# Main.net
KiCad netlist of a schematic drawn in Altium Designer
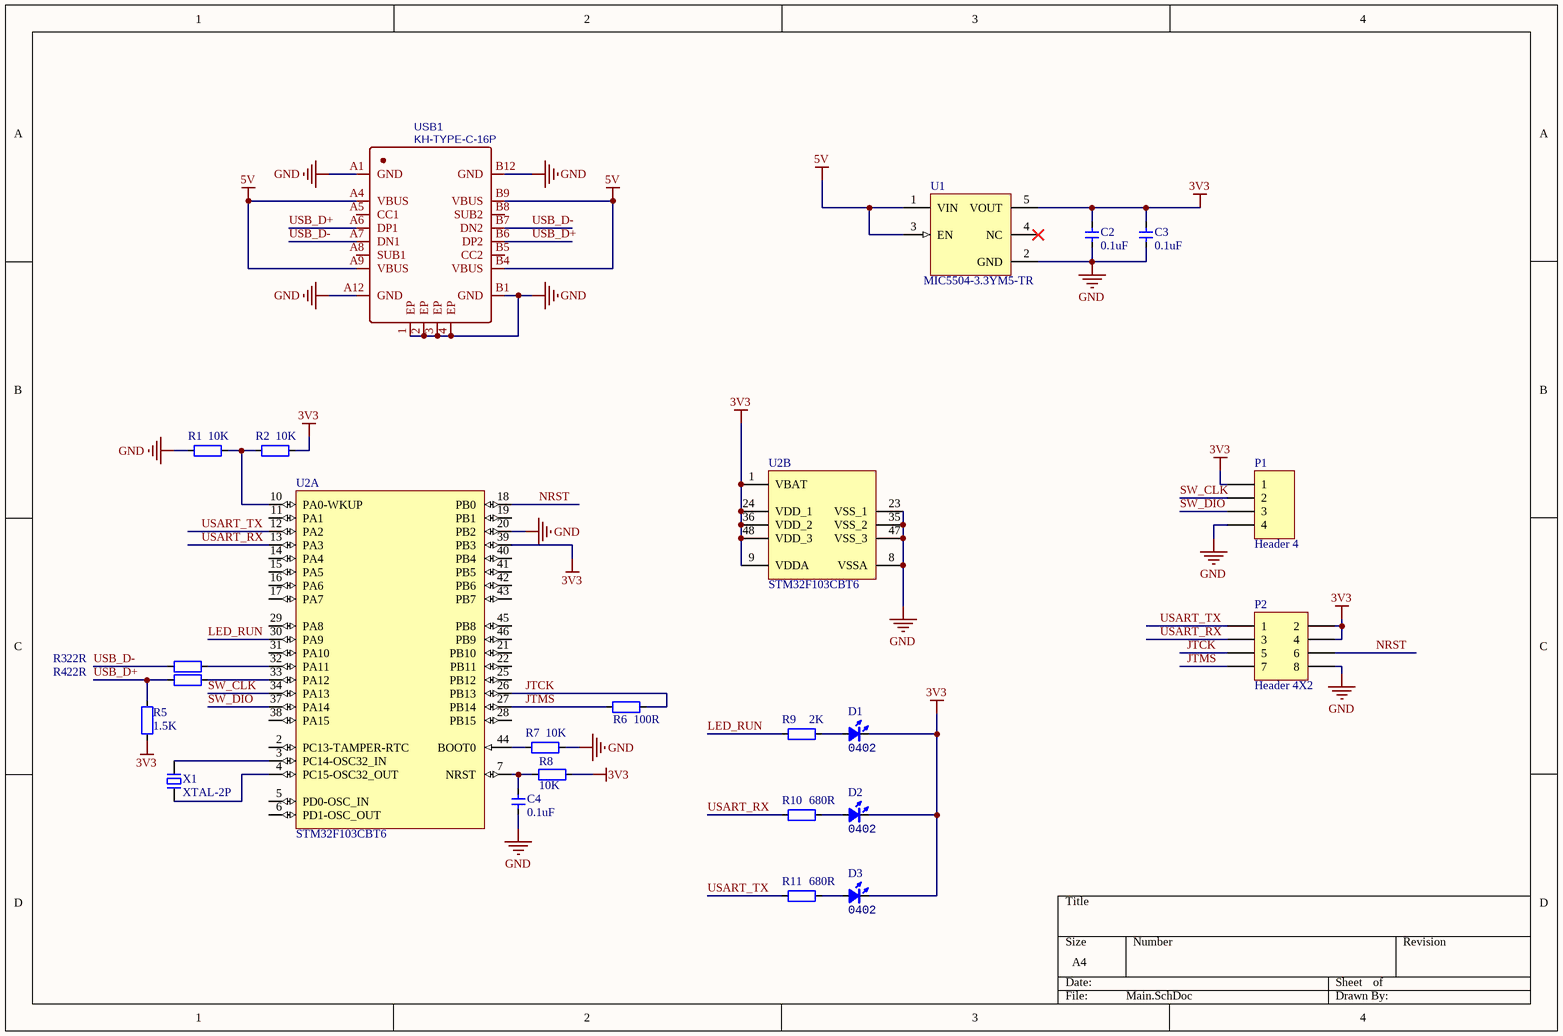
[diagram p0: Main.SchDoc]

(export (version "E")
  (design (tool "Eeschema 10.0.6"))
  (components
    (comp (ref "C2")
      (value "0.1uF")
      (footprint "CAP_0402")
      (description "Capacitor")
      (libsource (lib "My_SchLib") (part "电容-0402"))
    )
    (comp (ref "C3")
      (value "0.1uF")
      (footprint "CAP_0402")
      (description "Capacitor")
      (libsource (lib "My_SchLib") (part "电容-0402"))
    )
    (comp (ref "C4")
      (value "0.1uF")
      (footprint "CAP_0402")
      (description "Capacitor")
      (libsource (lib "My_SchLib") (part "电容-0402"))
    )
    (comp (ref "D1")
      (value "color?")
      (footprint "LED_0402_BLUE")
      (description "LED")
      (fields (field (name "TYPE") "0402"))
      (libsource (lib "KitSprout") (part "LED_0402"))
    )
    (comp (ref "D2")
      (value "color?")
      (footprint "LED_0402_BLUE")
      (description "LED")
      (fields (field (name "TYPE") "0402"))
      (libsource (lib "KitSprout") (part "LED_0402"))
    )
    (comp (ref "D3")
      (value "color?")
      (footprint "LED_0402_BLUE")
      (description "LED")
      (fields (field (name "TYPE") "0402"))
      (libsource (lib "KitSprout") (part "LED_0402"))
    )
    (comp (ref "P1")
      (value "Header 4")
      (footprint "TP-2.54-4P")
      (description "Header, 4-Pin")
      (fields (field (name "PUBLISHER") "Altium Limited"))
      (libsource (lib "Miscellaneous Connectors") (part "Header 4"))
    )
    (comp (ref "P2")
      (value "Header 4X2")
      (footprint "HDR2X4_2.54_180H")
      (description "Header, 4-Pin, Dual row")
      (fields (field (name "PUBLISHER") "Altium Limited"))
      (libsource (lib "Miscellaneous Connectors") (part "Header 4X2"))
    )
    (comp (ref "R1")
      (value "10K")
      (footprint "RES_0402")
      (description "Resistor")
      (libsource (lib "MyPcbLib") (part "电阻-0402"))
    )
    (comp (ref "R2")
      (value "10K")
      (footprint "RES_0402")
      (description "Resistor")
      (libsource (lib "MyPcbLib") (part "电阻-0402"))
    )
    (comp (ref "R3")
      (value "22R")
      (footprint "RES_0402")
      (description "Resistor")
      (libsource (lib "MyPcbLib") (part "电阻-0402"))
    )
    (comp (ref "R4")
      (value "22R")
      (footprint "RES_0402")
      (description "Resistor")
      (libsource (lib "MyPcbLib") (part "电阻-0402"))
    )
    (comp (ref "R5")
      (value "1.5K")
      (footprint "RES_0402")
      (description "Resistor")
      (libsource (lib "") (part "电阻-0402_1"))
    )
    (comp (ref "R6")
      (value "100R")
      (footprint "RES_0402")
      (description "Resistor")
      (libsource (lib "MyPcbLib") (part "电阻-0402"))
    )
    (comp (ref "R7")
      (value "10K")
      (footprint "RES_0402")
      (description "Resistor")
      (libsource (lib "MyPcbLib") (part "电阻-0402"))
    )
    (comp (ref "R8")
      (value "10K")
      (footprint "RES_0402")
      (description "Resistor")
      (libsource (lib "MyPcbLib") (part "电阻-0402"))
    )
    (comp (ref "R9")
      (value "2K")
      (footprint "RES_0402")
      (description "Resistor")
      (libsource (lib "MyPcbLib") (part "电阻-0402"))
    )
    (comp (ref "R10")
      (value "680R")
      (footprint "RES_0402")
      (description "Resistor")
      (libsource (lib "MyPcbLib") (part "电阻-0402"))
    )
    (comp (ref "R11")
      (value "680R")
      (footprint "RES_0402")
      (description "Resistor")
      (libsource (lib "MyPcbLib") (part "电阻-0402"))
    )
    (comp (ref "U1")
      (value "MIC5504-3.3YM5-TR")
      (footprint "MCHP-SOT-23-M5_V")
      (fields (field (name "MANUFACTURER") "Microchip"))
      (libsource (lib "Altium Content Vault") (part "MCHP-MIC5504-SOT-23-M5"))
    )
    (comp (ref "U2")
      (value "STM32F103CBT6")
      (footprint "LQFP-48")
      (libsource (lib "Altium Content Vault") (part "MC-ARM-STM32F103X8_B-SQ48"))
    )
    (comp (ref "USB1")
      (value "KH-TYPE-C-16P")
      (footprint "Type-C-SMD-16P-TOP")
      (fields (field (name "BOM_SUPPLIER PART") "C709357") (field (name "CONTRIBUTOR") "LCSC"))
      (libsource (lib "M_ST_Link") (part "KH-TYPE-C-16P"))
    )
    (comp (ref "X1")
      (value "XTAL-2P")
      (footprint "OSC 5032-2P")
      (description "2脚无源脚晶振")
      (libsource (lib "晶振") (part "XTAL-2P"))
    )
  )
  (nets
    (net (code "2") (name "/JTCK") (class "Default")
      (node (ref "P2") (pin "5") (pinfunction "5_5") (pintype "passive"))
      (node (ref "R6") (pin "2") (pinfunction "2_2") (pintype "passive"))
      (node (ref "U2") (pin "26") (pinfunction "PB13_26") (pintype "bidirectional"))
    )
    (net (code "3") (name "/JTMS") (class "Default")
      (node (ref "P2") (pin "7") (pinfunction "7_7") (pintype "passive"))
      (node (ref "R6") (pin "1") (pinfunction "1_1") (pintype "passive"))
      (node (ref "U2") (pin "27") (pinfunction "PB14_27") (pintype "bidirectional"))
    )
    (net (code "4") (name "/LED_RUN") (class "Default")
      (node (ref "R9") (pin "1") (pinfunction "1_1") (pintype "passive"))
      (node (ref "U2") (pin "30") (pinfunction "PA9_30") (pintype "bidirectional"))
    )
    (net (code "5") (name "/NRST") (class "Default")
      (node (ref "P2") (pin "6") (pinfunction "6_6") (pintype "passive"))
      (node (ref "U2") (pin "18") (pinfunction "PB0_18") (pintype "bidirectional"))
    )
    (net (code "6") (name "/SW_CLK") (class "Default")
      (node (ref "P1") (pin "2") (pinfunction "2_2") (pintype "passive"))
      (node (ref "U2") (pin "34") (pinfunction "PA13_34") (pintype "bidirectional"))
    )
    (net (code "7") (name "/SW_DIO") (class "Default")
      (node (ref "P1") (pin "3") (pinfunction "3_3") (pintype "passive"))
      (node (ref "U2") (pin "37") (pinfunction "PA14_37") (pintype "bidirectional"))
    )
    (net (code "8") (name "/USART_RX") (class "Default")
      (node (ref "P2") (pin "3") (pinfunction "3_3") (pintype "passive"))
      (node (ref "R10") (pin "1") (pinfunction "1_1") (pintype "passive"))
      (node (ref "U2") (pin "13") (pinfunction "PA3_13") (pintype "bidirectional"))
    )
    (net (code "9") (name "/USART_TX") (class "Default")
      (node (ref "P2") (pin "1") (pinfunction "1_1") (pintype "passive"))
      (node (ref "R11") (pin "1") (pinfunction "1_1") (pintype "passive"))
      (node (ref "U2") (pin "12") (pinfunction "PA2_12") (pintype "bidirectional"))
    )
    (net (code "10") (name "/USB_D+") (class "Default")
      (node (ref "R4") (pin "1") (pinfunction "1_1") (pintype "passive"))
      (node (ref "R5") (pin "2") (pinfunction "2_2") (pintype "passive"))
      (node (ref "USB1") (pin "A6") (pinfunction "DP1_A6") (pintype "passive"))
      (node (ref "USB1") (pin "B6") (pinfunction "DP2_B6") (pintype "passive"))
    )
    (net (code "11") (name "/USB_D-") (class "Default")
      (node (ref "R3") (pin "1") (pinfunction "1_1") (pintype "passive"))
      (node (ref "USB1") (pin "A7") (pinfunction "DN1_A7") (pintype "passive"))
      (node (ref "USB1") (pin "B7") (pinfunction "DN2_B7") (pintype "passive"))
    )
    (net (code "12") (name "3V3") (class "Default")
      (node (ref "C2") (pin "2") (pinfunction "2_2") (pintype "passive"))
      (node (ref "C3") (pin "2") (pinfunction "2_2") (pintype "passive"))
      (node (ref "D1") (pin "2") (pinfunction "K_2") (pintype "passive"))
      (node (ref "D2") (pin "2") (pinfunction "K_2") (pintype "passive"))
      (node (ref "D3") (pin "2") (pinfunction "K_2") (pintype "passive"))
      (node (ref "P1") (pin "1") (pinfunction "1_1") (pintype "passive"))
      (node (ref "P2") (pin "2") (pinfunction "2_2") (pintype "passive"))
      (node (ref "P2") (pin "4") (pinfunction "4_4") (pintype "passive"))
      (node (ref "R2") (pin "2") (pinfunction "2_2") (pintype "passive"))
      (node (ref "R5") (pin "1") (pinfunction "1_1") (pintype "passive"))
      (node (ref "R8") (pin "2") (pinfunction "2_2") (pintype "passive"))
      (node (ref "U1") (pin "5") (pinfunction "VOUT_5") (pintype "power_in"))
      (node (ref "U2") (pin "1") (pinfunction "VBAT_1") (pintype "power_in"))
      (node (ref "U2") (pin "24") (pinfunction "VDD_1_24") (pintype "power_in"))
      (node (ref "U2") (pin "36") (pinfunction "VDD_2_36") (pintype "power_in"))
      (node (ref "U2") (pin "39") (pinfunction "PB3_39") (pintype "bidirectional"))
      (node (ref "U2") (pin "48") (pinfunction "VDD_3_48") (pintype "power_in"))
      (node (ref "U2") (pin "9") (pinfunction "VDDA_9") (pintype "power_in"))
    )
    (net (code "13") (name "5V") (class "Default")
      (node (ref "U1") (pin "1") (pinfunction "VIN_1") (pintype "power_in"))
      (node (ref "U1") (pin "3") (pinfunction "EN_3") (pintype "input"))
      (node (ref "USB1") (pin "A4") (pinfunction "VBUS_A4") (pintype "passive"))
      (node (ref "USB1") (pin "A9") (pinfunction "VBUS_A9") (pintype "passive"))
      (node (ref "USB1") (pin "B4") (pinfunction "VBUS_B4") (pintype "passive"))
      (node (ref "USB1") (pin "B9") (pinfunction "VBUS_B9") (pintype "passive"))
    )
    (net (code "14") (name "GND") (class "Default")
      (node (ref "C2") (pin "1") (pinfunction "1_1") (pintype "passive"))
      (node (ref "C3") (pin "1") (pinfunction "1_1") (pintype "passive"))
      (node (ref "C4") (pin "1") (pinfunction "1_1") (pintype "passive"))
      (node (ref "P1") (pin "4") (pinfunction "4_4") (pintype "passive"))
      (node (ref "P2") (pin "8") (pinfunction "8_8") (pintype "passive"))
      (node (ref "R1") (pin "1") (pinfunction "1_1") (pintype "passive"))
      (node (ref "R7") (pin "2") (pinfunction "2_2") (pintype "passive"))
      (node (ref "U1") (pin "2") (pinfunction "GND_2") (pintype "power_in"))
      (node (ref "U2") (pin "20") (pinfunction "PB2_20") (pintype "bidirectional"))
      (node (ref "U2") (pin "23") (pinfunction "VSS_1_23") (pintype "power_in"))
      (node (ref "U2") (pin "35") (pinfunction "VSS_2_35") (pintype "power_in"))
      (node (ref "U2") (pin "47") (pinfunction "VSS_3_47") (pintype "power_in"))
      (node (ref "U2") (pin "8") (pinfunction "VSSA_8") (pintype "power_in"))
      (node (ref "USB1") (pin "1") (pinfunction "EP_1") (pintype "passive"))
      (node (ref "USB1") (pin "2") (pinfunction "EP_2") (pintype "passive"))
      (node (ref "USB1") (pin "3") (pinfunction "EP_3") (pintype "passive"))
      (node (ref "USB1") (pin "4") (pinfunction "EP_4") (pintype "passive"))
      (node (ref "USB1") (pin "A1") (pinfunction "GND_A1") (pintype "passive"))
      (node (ref "USB1") (pin "A12") (pinfunction "GND_A12") (pintype "passive"))
      (node (ref "USB1") (pin "B1") (pinfunction "GND_B1") (pintype "passive"))
      (node (ref "USB1") (pin "B12") (pinfunction "GND_B12") (pintype "passive"))
    )
    (net (code "15") (name "Net-(D1-A)") (class "Default")
      (node (ref "D1") (pin "1") (pinfunction "A_1") (pintype "passive"))
      (node (ref "R9") (pin "2") (pinfunction "2_2") (pintype "passive"))
    )
    (net (code "16") (name "Net-(D2-A)") (class "Default")
      (node (ref "D2") (pin "1") (pinfunction "A_1") (pintype "passive"))
      (node (ref "R10") (pin "2") (pinfunction "2_2") (pintype "passive"))
    )
    (net (code "17") (name "Net-(D3-A)") (class "Default")
      (node (ref "D3") (pin "1") (pinfunction "A_1") (pintype "passive"))
      (node (ref "R11") (pin "2") (pinfunction "2_2") (pintype "passive"))
    )
    (net (code "18") (name "Net-(U2A-BOOT0)") (class "Default")
      (node (ref "R7") (pin "1") (pinfunction "1_1") (pintype "passive"))
      (node (ref "U2") (pin "44") (pinfunction "BOOT0_44") (pintype "input"))
    )
    (net (code "19") (name "Net-(U2A-NRST)") (class "Default")
      (node (ref "C4") (pin "2") (pinfunction "2_2") (pintype "passive"))
      (node (ref "R8") (pin "1") (pinfunction "1_1") (pintype "passive"))
      (node (ref "U2") (pin "7") (pinfunction "NRST_7") (pintype "bidirectional"))
    )
    (net (code "20") (name "Net-(U2A-PA0-WKUP)") (class "Default")
      (node (ref "R1") (pin "2") (pinfunction "2_2") (pintype "passive"))
      (node (ref "R2") (pin "1") (pinfunction "1_1") (pintype "passive"))
      (node (ref "U2") (pin "10") (pinfunction "PA0-WKUP_10") (pintype "bidirectional"))
    )
    (net (code "21") (name "Net-(U2A-PA11)") (class "Default")
      (node (ref "R3") (pin "2") (pinfunction "2_2") (pintype "passive"))
      (node (ref "U2") (pin "32") (pinfunction "PA11_32") (pintype "bidirectional"))
    )
    (net (code "22") (name "Net-(U2A-PA12)") (class "Default")
      (node (ref "R4") (pin "2") (pinfunction "2_2") (pintype "passive"))
      (node (ref "U2") (pin "33") (pinfunction "PA12_33") (pintype "bidirectional"))
    )
    (net (code "23") (name "Net-(U2A-PC14-OSC32_IN)") (class "Default")
      (node (ref "U2") (pin "3") (pinfunction "PC14-OSC32_IN_3") (pintype "bidirectional"))
      (node (ref "X1") (pin "2") (pinfunction "2_2") (pintype "passive"))
    )
    (net (code "24") (name "Net-(U2A-PC15-OSC32_OUT)") (class "Default")
      (node (ref "U2") (pin "4") (pinfunction "PC15-OSC32_OUT_4") (pintype "bidirectional"))
      (node (ref "X1") (pin "1") (pinfunction "1_1") (pintype "passive"))
    )
    (net (code "25") (name "unconnected-(U1-NC-Pad4)") (class "Default")
      (node (ref "U1") (pin "4") (pinfunction "NC_4") (pintype "passive+no_connect"))
    )
    (net (code "26") (name "unconnected-(U2A-PA1-Pad11)") (class "Default")
      (node (ref "U2") (pin "11") (pinfunction "PA1_11") (pintype "bidirectional"))
    )
    (net (code "27") (name "unconnected-(U2A-PA4-Pad14)") (class "Default")
      (node (ref "U2") (pin "14") (pinfunction "PA4_14") (pintype "bidirectional"))
    )
    (net (code "28") (name "unconnected-(U2A-PA5-Pad15)") (class "Default")
      (node (ref "U2") (pin "15") (pinfunction "PA5_15") (pintype "bidirectional"))
    )
    (net (code "29") (name "unconnected-(U2A-PA6-Pad16)") (class "Default")
      (node (ref "U2") (pin "16") (pinfunction "PA6_16") (pintype "bidirectional"))
    )
    (net (code "30") (name "unconnected-(U2A-PA7-Pad17)") (class "Default")
      (node (ref "U2") (pin "17") (pinfunction "PA7_17") (pintype "bidirectional"))
    )
    (net (code "31") (name "unconnected-(U2A-PA8-Pad29)") (class "Default")
      (node (ref "U2") (pin "29") (pinfunction "PA8_29") (pintype "bidirectional"))
    )
    (net (code "32") (name "unconnected-(U2A-PA10-Pad31)") (class "Default")
      (node (ref "U2") (pin "31") (pinfunction "PA10_31") (pintype "bidirectional"))
    )
    (net (code "33") (name "unconnected-(U2A-PA15-Pad38)") (class "Default")
      (node (ref "U2") (pin "38") (pinfunction "PA15_38") (pintype "bidirectional"))
    )
    (net (code "34") (name "unconnected-(U2A-PB1-Pad19)") (class "Default")
      (node (ref "U2") (pin "19") (pinfunction "PB1_19") (pintype "bidirectional"))
    )
    (net (code "35") (name "unconnected-(U2A-PB4-Pad40)") (class "Default")
      (node (ref "U2") (pin "40") (pinfunction "PB4_40") (pintype "bidirectional"))
    )
    (net (code "36") (name "unconnected-(U2A-PB5-Pad41)") (class "Default")
      (node (ref "U2") (pin "41") (pinfunction "PB5_41") (pintype "bidirectional"))
    )
    (net (code "37") (name "unconnected-(U2A-PB6-Pad42)") (class "Default")
      (node (ref "U2") (pin "42") (pinfunction "PB6_42") (pintype "bidirectional"))
    )
    (net (code "38") (name "unconnected-(U2A-PB7-Pad43)") (class "Default")
      (node (ref "U2") (pin "43") (pinfunction "PB7_43") (pintype "bidirectional"))
    )
    (net (code "39") (name "unconnected-(U2A-PB8-Pad45)") (class "Default")
      (node (ref "U2") (pin "45") (pinfunction "PB8_45") (pintype "bidirectional"))
    )
    (net (code "40") (name "unconnected-(U2A-PB9-Pad46)") (class "Default")
      (node (ref "U2") (pin "46") (pinfunction "PB9_46") (pintype "bidirectional"))
    )
    (net (code "41") (name "unconnected-(U2A-PB10-Pad21)") (class "Default")
      (node (ref "U2") (pin "21") (pinfunction "PB10_21") (pintype "bidirectional"))
    )
    (net (code "42") (name "unconnected-(U2A-PB11-Pad22)") (class "Default")
      (node (ref "U2") (pin "22") (pinfunction "PB11_22") (pintype "bidirectional"))
    )
    (net (code "43") (name "unconnected-(U2A-PB12-Pad25)") (class "Default")
      (node (ref "U2") (pin "25") (pinfunction "PB12_25") (pintype "bidirectional"))
    )
    (net (code "44") (name "unconnected-(U2A-PB15-Pad28)") (class "Default")
      (node (ref "U2") (pin "28") (pinfunction "PB15_28") (pintype "bidirectional"))
    )
    (net (code "45") (name "unconnected-(U2A-PC13-TAMPER-RTC-Pad2)") (class "Default")
      (node (ref "U2") (pin "2") (pinfunction "PC13-TAMPER-RTC_2") (pintype "bidirectional"))
    )
    (net (code "46") (name "unconnected-(U2A-PD0-OSC_IN-Pad5)") (class "Default")
      (node (ref "U2") (pin "5") (pinfunction "PD0-OSC_IN_5") (pintype "bidirectional"))
    )
    (net (code "47") (name "unconnected-(U2A-PD1-OSC_OUT-Pad6)") (class "Default")
      (node (ref "U2") (pin "6") (pinfunction "PD1-OSC_OUT_6") (pintype "bidirectional"))
    )
    (net (code "48") (name "unconnected-(USB1-CC1-PadA5)") (class "Default")
      (node (ref "USB1") (pin "A5") (pinfunction "CC1_A5") (pintype "passive"))
    )
    (net (code "49") (name "unconnected-(USB1-CC2-PadB5)") (class "Default")
      (node (ref "USB1") (pin "B5") (pinfunction "CC2_B5") (pintype "passive"))
    )
    (net (code "50") (name "unconnected-(USB1-SUB1-PadA8)") (class "Default")
      (node (ref "USB1") (pin "A8") (pinfunction "SUB1_A8") (pintype "passive"))
    )
    (net (code "51") (name "unconnected-(USB1-SUB2-PadB8)") (class "Default")
      (node (ref "USB1") (pin "B8") (pinfunction "SUB2_B8") (pintype "passive"))
    )
  )
)
